# pilot.net
KiCad netlist of a schematic drawn in EAGLE
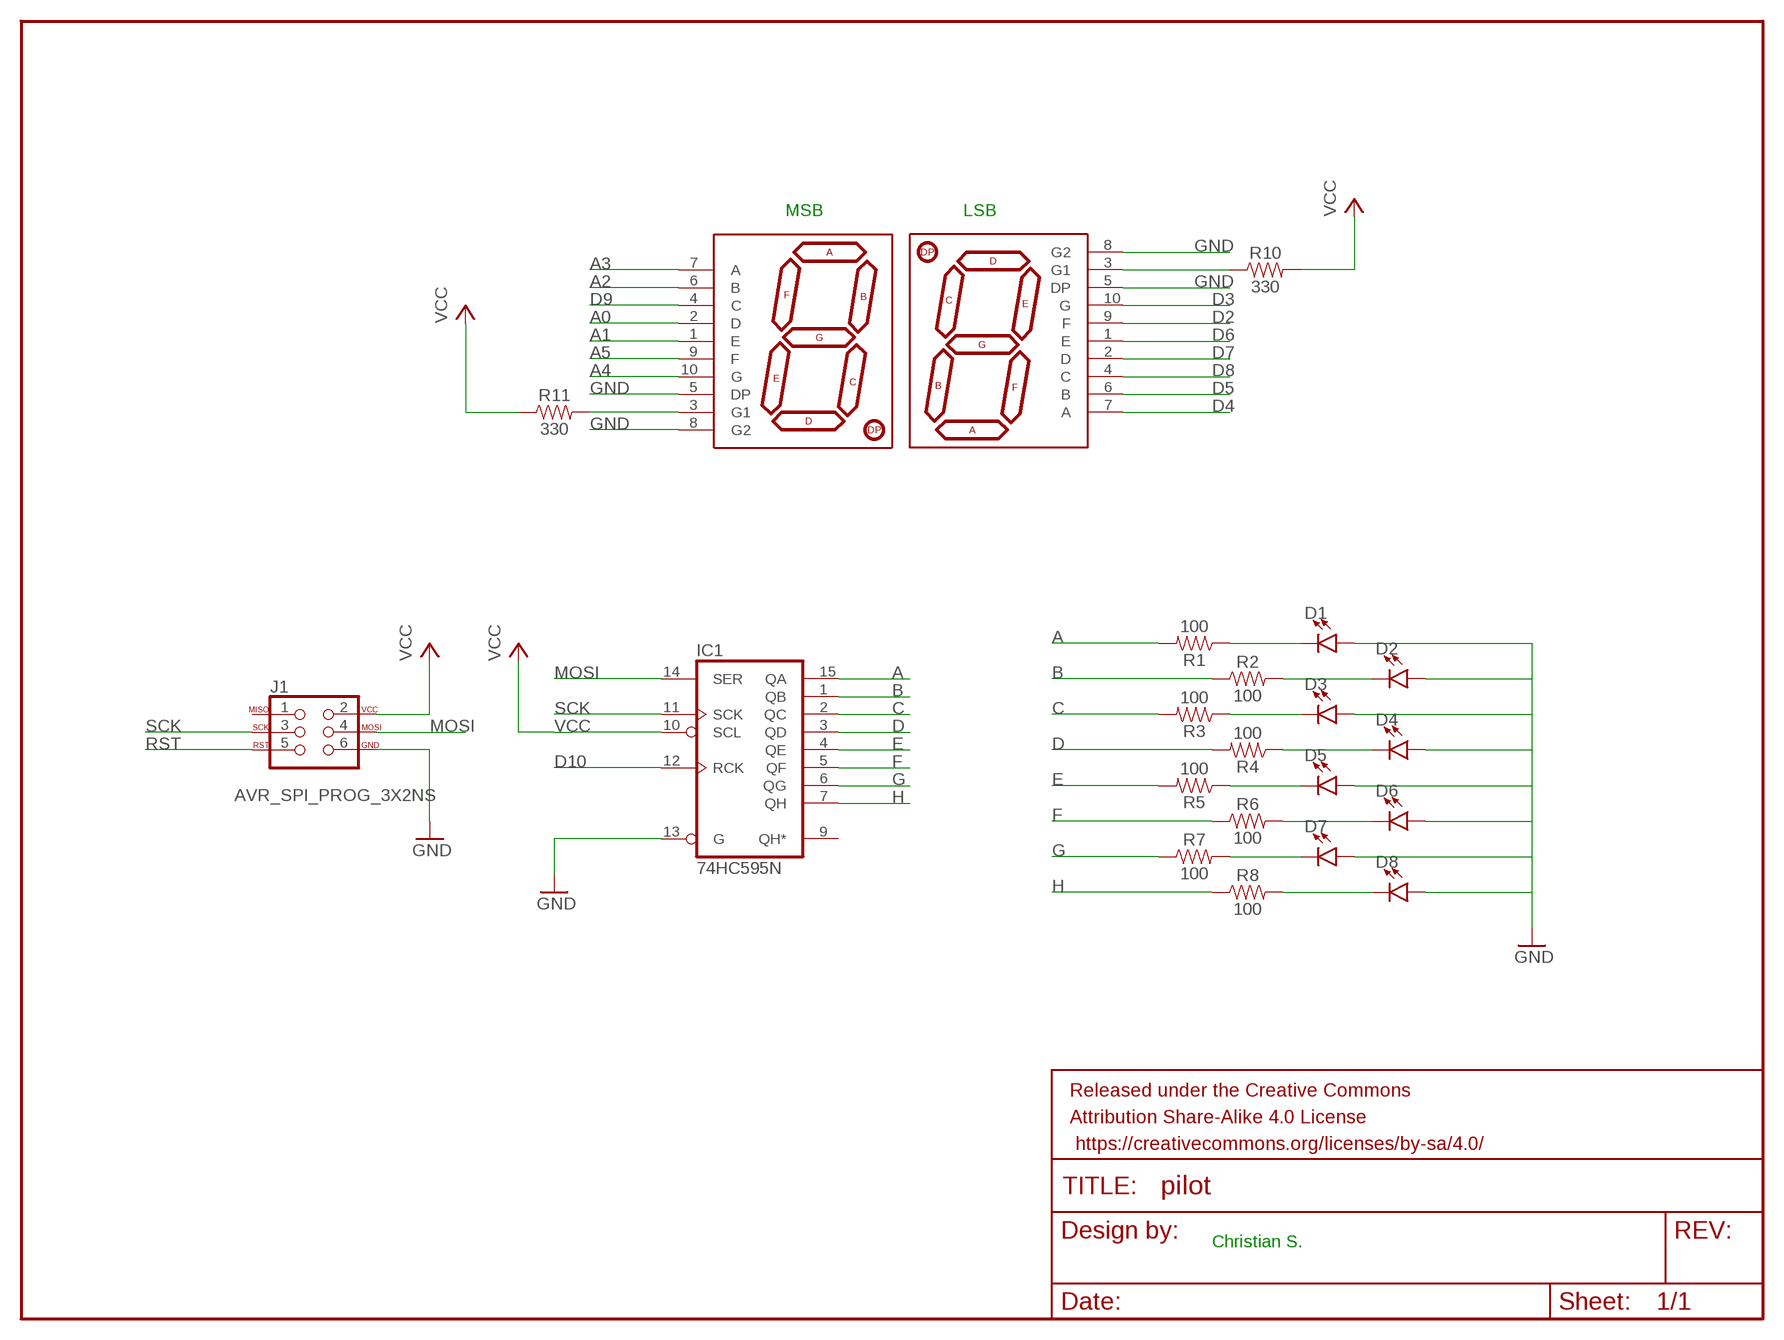
[diagram p0: schematic, sheet 1]

(export (version "E")
  (design (tool "Eeschema 10.0.6"))
  (components
    (comp (ref "D1")
      (value "LED3MM")
      (footprint "eagle-import:LED_3MM")
      (libsource (lib "eagle-import") (part "LED3MM"))
    )
    (comp (ref "D2")
      (value "LED3MM")
      (footprint "eagle-import:LED_3MM")
      (libsource (lib "eagle-import") (part "LED3MM"))
    )
    (comp (ref "D3")
      (value "LED3MM")
      (footprint "eagle-import:LED_3MM")
      (libsource (lib "eagle-import") (part "LED3MM"))
    )
    (comp (ref "D4")
      (value "LED3MM")
      (footprint "eagle-import:LED_3MM")
      (libsource (lib "eagle-import") (part "LED3MM"))
    )
    (comp (ref "D5")
      (value "LED3MM")
      (footprint "eagle-import:LED_3MM")
      (libsource (lib "eagle-import") (part "LED3MM"))
    )
    (comp (ref "D6")
      (value "LED3MM")
      (footprint "eagle-import:LED_3MM")
      (libsource (lib "eagle-import") (part "LED3MM"))
    )
    (comp (ref "D7")
      (value "LED3MM")
      (footprint "eagle-import:LED_3MM")
      (libsource (lib "eagle-import") (part "LED3MM"))
    )
    (comp (ref "D8")
      (value "LED3MM")
      (footprint "eagle-import:LED_3MM")
      (libsource (lib "eagle-import") (part "LED3MM"))
    )
    (comp (ref "FRAME1")
      (value "FRAME-LETTER")
      (footprint "eagle-import:CREATIVE_COMMONS")
      (libsource (lib "eagle-import") (part "FRAME-LETTER"))
    )
    (comp (ref "IC1")
      (value "74HC595N")
      (footprint "eagle-import:DIL16")
      (libsource (lib "eagle-import") (part "74595NHC"))
    )
    (comp (ref "J1")
      (value "AVR_SPI_PROG_3X2NS")
      (footprint "eagle-import:2X3-NS")
      (libsource (lib "eagle-import") (part "AVR_SPI_PROG_3X2NS"))
    )
    (comp (ref "R1")
      (value "100")
      (footprint "eagle-import:0603")
      (libsource (lib "eagle-import") (part "10OHM-0603-1/10W-1%"))
    )
    (comp (ref "R2")
      (value "100")
      (footprint "eagle-import:0603")
      (libsource (lib "eagle-import") (part "10OHM-0603-1/10W-1%"))
    )
    (comp (ref "R3")
      (value "100")
      (footprint "eagle-import:0603")
      (libsource (lib "eagle-import") (part "10OHM-0603-1/10W-1%"))
    )
    (comp (ref "R4")
      (value "100")
      (footprint "eagle-import:0603")
      (libsource (lib "eagle-import") (part "10OHM-0603-1/10W-1%"))
    )
    (comp (ref "R5")
      (value "100")
      (footprint "eagle-import:0603")
      (libsource (lib "eagle-import") (part "10OHM-0603-1/10W-1%"))
    )
    (comp (ref "R6")
      (value "100")
      (footprint "eagle-import:0603")
      (libsource (lib "eagle-import") (part "10OHM-0603-1/10W-1%"))
    )
    (comp (ref "R7")
      (value "100")
      (footprint "eagle-import:0603")
      (libsource (lib "eagle-import") (part "10OHM-0603-1/10W-1%"))
    )
    (comp (ref "R8")
      (value "100")
      (footprint "eagle-import:0603")
      (libsource (lib "eagle-import") (part "10OHM-0603-1/10W-1%"))
    )
    (comp (ref "R10")
      (value "330")
      (footprint "eagle-import:0603")
      (libsource (lib "eagle-import") (part "330OHM-0603-1/10W-1%"))
    )
    (comp (ref "R11")
      (value "330")
      (footprint "eagle-import:0603")
      (libsource (lib "eagle-import") (part "330OHM-0603-1/10W-1%"))
    )
    (comp (ref "U$1")
      (value "YSD-160AB3C-8")
      (footprint "eagle-import:7-SEGMENT-1_PTH")
      (libsource (lib "eagle-import") (part "7-SEGMENT-1DIGIT-1INCH-BLUE"))
    )
    (comp (ref "U$2")
      (value "YSD-160AB3C-8")
      (footprint "eagle-import:7-SEGMENT-1_PTH")
      (libsource (lib "eagle-import") (part "7-SEGMENT-1DIGIT-1INCH-BLUE"))
    )
  )
  (nets
    (net (code "1") (name "/A") (class "Default")
      (node (ref "IC1") (pin "15") (pinfunction "QA_15") (pintype "tri_state"))
      (node (ref "R1") (pin "2") (pinfunction "2_2") (pintype "passive"))
    )
    (net (code "2") (name "/A0") (class "Default")
      (node (ref "U$1") (pin "2") (pinfunction "D_2") (pintype "bidirectional"))
    )
    (net (code "3") (name "/A1") (class "Default")
      (node (ref "U$1") (pin "1") (pinfunction "E_1") (pintype "bidirectional"))
    )
    (net (code "4") (name "/A2") (class "Default")
      (node (ref "U$1") (pin "6") (pinfunction "B_6") (pintype "bidirectional"))
    )
    (net (code "5") (name "/A3") (class "Default")
      (node (ref "U$1") (pin "7") (pinfunction "A_7") (pintype "bidirectional"))
    )
    (net (code "6") (name "/A4") (class "Default")
      (node (ref "U$1") (pin "10") (pinfunction "G_10") (pintype "bidirectional"))
    )
    (net (code "7") (name "/A5") (class "Default")
      (node (ref "U$1") (pin "9") (pinfunction "F_9") (pintype "bidirectional"))
    )
    (net (code "8") (name "/B") (class "Default")
      (node (ref "IC1") (pin "1") (pinfunction "QB_1") (pintype "tri_state"))
      (node (ref "R2") (pin "1") (pinfunction "1_1") (pintype "passive"))
    )
    (net (code "9") (name "/C") (class "Default")
      (node (ref "IC1") (pin "2") (pinfunction "QC_2") (pintype "tri_state"))
      (node (ref "R3") (pin "2") (pinfunction "2_2") (pintype "passive"))
    )
    (net (code "10") (name "/D") (class "Default")
      (node (ref "IC1") (pin "3") (pinfunction "QD_3") (pintype "tri_state"))
      (node (ref "R4") (pin "2") (pinfunction "2_2") (pintype "passive"))
    )
    (net (code "11") (name "/D2") (class "Default")
      (node (ref "U$2") (pin "9") (pinfunction "F_9") (pintype "bidirectional"))
    )
    (net (code "12") (name "/D3") (class "Default")
      (node (ref "U$2") (pin "10") (pinfunction "G_10") (pintype "bidirectional"))
    )
    (net (code "13") (name "/D4") (class "Default")
      (node (ref "U$2") (pin "7") (pinfunction "A_7") (pintype "bidirectional"))
    )
    (net (code "14") (name "/D5") (class "Default")
      (node (ref "U$2") (pin "6") (pinfunction "B_6") (pintype "bidirectional"))
    )
    (net (code "15") (name "/D6") (class "Default")
      (node (ref "U$2") (pin "1") (pinfunction "E_1") (pintype "bidirectional"))
    )
    (net (code "16") (name "/D7") (class "Default")
      (node (ref "U$2") (pin "2") (pinfunction "D_2") (pintype "bidirectional"))
    )
    (net (code "17") (name "/D8") (class "Default")
      (node (ref "U$2") (pin "4") (pinfunction "C_4") (pintype "bidirectional"))
    )
    (net (code "18") (name "/D9") (class "Default")
      (node (ref "U$1") (pin "4") (pinfunction "C_4") (pintype "bidirectional"))
    )
    (net (code "19") (name "/D10") (class "Default")
      (node (ref "IC1") (pin "12") (pinfunction "RCK_12") (pintype "input"))
    )
    (net (code "20") (name "/E") (class "Default")
      (node (ref "IC1") (pin "4") (pinfunction "QE_4") (pintype "tri_state"))
      (node (ref "R5") (pin "2") (pinfunction "2_2") (pintype "passive"))
    )
    (net (code "21") (name "/F") (class "Default")
      (node (ref "IC1") (pin "5") (pinfunction "QF_5") (pintype "tri_state"))
      (node (ref "R6") (pin "1") (pinfunction "1_1") (pintype "passive"))
    )
    (net (code "22") (name "/G") (class "Default")
      (node (ref "IC1") (pin "6") (pinfunction "QG_6") (pintype "tri_state"))
      (node (ref "R7") (pin "1") (pinfunction "1_1") (pintype "passive"))
    )
    (net (code "23") (name "/H") (class "Default")
      (node (ref "IC1") (pin "7") (pinfunction "QH_7") (pintype "tri_state"))
      (node (ref "R8") (pin "1") (pinfunction "1_1") (pintype "passive"))
    )
    (net (code "24") (name "/MOSI") (class "Default")
      (node (ref "IC1") (pin "14") (pinfunction "SER_14") (pintype "input"))
      (node (ref "J1") (pin "4") (pinfunction "4_4") (pintype "passive"))
    )
    (net (code "25") (name "/RST") (class "Default")
      (node (ref "J1") (pin "5") (pinfunction "5_5") (pintype "passive"))
    )
    (net (code "26") (name "/SCK") (class "Default")
      (node (ref "IC1") (pin "11") (pinfunction "SCK_11") (pintype "input"))
      (node (ref "J1") (pin "3") (pinfunction "3_3") (pintype "passive"))
    )
    (net (code "27") (name "GND") (class "Default")
      (node (ref "D1") (pin "A") (pinfunction "A_A") (pintype "passive"))
      (node (ref "D2") (pin "A") (pinfunction "A_A") (pintype "passive"))
      (node (ref "D3") (pin "A") (pinfunction "A_A") (pintype "passive"))
      (node (ref "D4") (pin "A") (pinfunction "A_A") (pintype "passive"))
      (node (ref "D5") (pin "A") (pinfunction "A_A") (pintype "passive"))
      (node (ref "D6") (pin "A") (pinfunction "A_A") (pintype "passive"))
      (node (ref "D7") (pin "A") (pinfunction "A_A") (pintype "passive"))
      (node (ref "D8") (pin "A") (pinfunction "A_A") (pintype "passive"))
      (node (ref "IC1") (pin "13") (pinfunction "G_13") (pintype "input"))
      (node (ref "J1") (pin "6") (pinfunction "6_6") (pintype "passive"))
      (node (ref "U$1") (pin "5") (pinfunction "DP_5") (pintype "bidirectional"))
      (node (ref "U$1") (pin "8") (pinfunction "G2_8") (pintype "bidirectional"))
      (node (ref "U$2") (pin "5") (pinfunction "DP_5") (pintype "bidirectional"))
      (node (ref "U$2") (pin "8") (pinfunction "G2_8") (pintype "bidirectional"))
    )
    (net (code "28") (name "Net-(D1-C)") (class "Default")
      (node (ref "D1") (pin "K") (pinfunction "C_K") (pintype "passive"))
      (node (ref "R1") (pin "1") (pinfunction "1_1") (pintype "passive"))
    )
    (net (code "29") (name "Net-(D2-C)") (class "Default")
      (node (ref "D2") (pin "K") (pinfunction "C_K") (pintype "passive"))
      (node (ref "R2") (pin "2") (pinfunction "2_2") (pintype "passive"))
    )
    (net (code "30") (name "Net-(D3-C)") (class "Default")
      (node (ref "D3") (pin "K") (pinfunction "C_K") (pintype "passive"))
      (node (ref "R3") (pin "1") (pinfunction "1_1") (pintype "passive"))
    )
    (net (code "31") (name "Net-(D4-C)") (class "Default")
      (node (ref "D4") (pin "K") (pinfunction "C_K") (pintype "passive"))
      (node (ref "R4") (pin "1") (pinfunction "1_1") (pintype "passive"))
    )
    (net (code "32") (name "Net-(D5-C)") (class "Default")
      (node (ref "D5") (pin "K") (pinfunction "C_K") (pintype "passive"))
      (node (ref "R5") (pin "1") (pinfunction "1_1") (pintype "passive"))
    )
    (net (code "33") (name "Net-(D6-C)") (class "Default")
      (node (ref "D6") (pin "K") (pinfunction "C_K") (pintype "passive"))
      (node (ref "R6") (pin "2") (pinfunction "2_2") (pintype "passive"))
    )
    (net (code "34") (name "Net-(D7-C)") (class "Default")
      (node (ref "D7") (pin "K") (pinfunction "C_K") (pintype "passive"))
      (node (ref "R7") (pin "2") (pinfunction "2_2") (pintype "passive"))
    )
    (net (code "35") (name "Net-(D8-C)") (class "Default")
      (node (ref "D8") (pin "K") (pinfunction "C_K") (pintype "passive"))
      (node (ref "R8") (pin "2") (pinfunction "2_2") (pintype "passive"))
    )
    (net (code "36") (name "Net-(U$1-G1)") (class "Default")
      (node (ref "R11") (pin "2") (pinfunction "2_2") (pintype "passive"))
      (node (ref "U$1") (pin "3") (pinfunction "G1_3") (pintype "bidirectional"))
    )
    (net (code "37") (name "Net-(U$2-G1)") (class "Default")
      (node (ref "R10") (pin "1") (pinfunction "1_1") (pintype "passive"))
      (node (ref "U$2") (pin "3") (pinfunction "G1_3") (pintype "bidirectional"))
    )
    (net (code "38") (name "VCC") (class "Default")
      (node (ref "IC1") (pin "10") (pinfunction "SCL_10") (pintype "input"))
      (node (ref "J1") (pin "2") (pinfunction "2_2") (pintype "passive"))
      (node (ref "R10") (pin "2") (pinfunction "2_2") (pintype "passive"))
      (node (ref "R11") (pin "1") (pinfunction "1_1") (pintype "passive"))
    )
    (net (code "39") (name "unconnected-(IC1A-QH*-Pad9)") (class "Default")
      (node (ref "IC1") (pin "9") (pinfunction "QH*_9") (pintype "tri_state"))
    )
    (net (code "40") (name "unconnected-(J1-Pad1)") (class "Default")
      (node (ref "J1") (pin "1") (pinfunction "1_1") (pintype "passive"))
    )
  )
)
